# esp32-driver.net
KiCad netlist of a schematic drawn in EAGLE
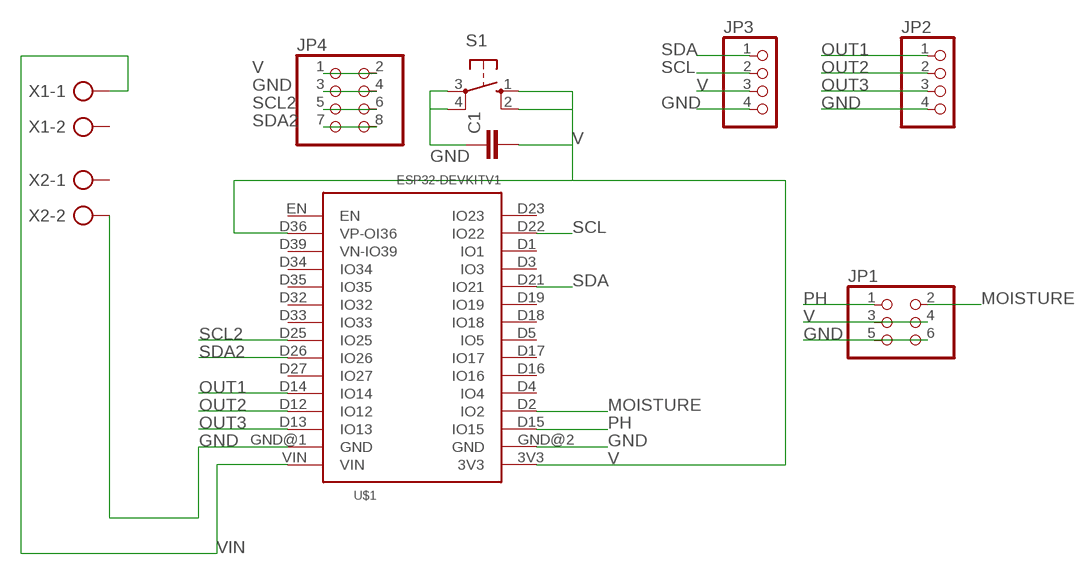
[diagram p0: schematic, sheet 1]

(export (version "E")
  (design (tool "Eeschema 10.0.6"))
  (components
    (comp (ref "C1")
      (value "C-EU050-030X075")
      (footprint "eagle-import:C050-030X075")
      (libsource (lib "eagle-import") (part "C-EU050-030X075"))
    )
    (comp (ref "JP1")
      (value "PINHD-2X3")
      (footprint "eagle-import:2X03")
      (libsource (lib "eagle-import") (part "PINHD-2X3"))
    )
    (comp (ref "JP2")
      (value "PINHD-1X4")
      (footprint "eagle-import:1X04")
      (libsource (lib "eagle-import") (part "PINHD-1X4"))
    )
    (comp (ref "JP3")
      (value "PINHD-1X4")
      (footprint "eagle-import:1X04")
      (libsource (lib "eagle-import") (part "PINHD-1X4"))
    )
    (comp (ref "JP4")
      (value "PINHD-2X4")
      (footprint "eagle-import:2X04")
      (libsource (lib "eagle-import") (part "PINHD-2X4"))
    )
    (comp (ref "S1")
      (value "10-XX")
      (footprint "eagle-import:B3F-10XX")
      (fields (field (name "MPN") "B3F-1000"))
      (libsource (lib "eagle-import") (part "10-XX"))
    )
    (comp (ref "U$1")
      (value "ESP32DEVKITV1")
      (footprint "eagle-import:ESP32-DEVKITV1")
      (libsource (lib "eagle-import") (part "ESP32DEVKITV1"))
    )
    (comp (ref "X1")
      (value "AK300/2")
      (footprint "eagle-import:AK300_2")
      (libsource (lib "eagle-import") (part "AK300/2"))
    )
    (comp (ref "X2")
      (value "AK300/2")
      (footprint "eagle-import:AK300_2")
      (libsource (lib "eagle-import") (part "AK300/2"))
    )
  )
  (nets
    (net (code "1") (name "/GND") (class "Default")
      (node (ref "C1") (pin "1") (pinfunction "1_1") (pintype "passive"))
      (node (ref "JP1") (pin "5") (pinfunction "5_5") (pintype "passive"))
      (node (ref "JP1") (pin "6") (pinfunction "6_6") (pintype "passive"))
      (node (ref "JP2") (pin "4") (pinfunction "4_4") (pintype "passive"))
      (node (ref "JP3") (pin "4") (pinfunction "4_4") (pintype "passive"))
      (node (ref "JP4") (pin "3") (pinfunction "3_3") (pintype "passive"))
      (node (ref "JP4") (pin "4") (pinfunction "4_4") (pintype "passive"))
      (node (ref "S1") (pin "3") (pinfunction "P_3") (pintype "passive"))
      (node (ref "S1") (pin "4") (pinfunction "P1_4") (pintype "passive"))
      (node (ref "U$1") (pin "GND@1") (pinfunction "GND_GND@1") (pintype "bidirectional"))
      (node (ref "U$1") (pin "GND@2") (pinfunction "GND_GND@2") (pintype "bidirectional"))
      (node (ref "X2") (pin "2") (pinfunction "KL_2") (pintype "passive"))
    )
    (net (code "2") (name "/MOISTURE") (class "Default")
      (node (ref "JP1") (pin "2") (pinfunction "2_2") (pintype "passive"))
      (node (ref "U$1") (pin "D2") (pinfunction "IO2_D2") (pintype "bidirectional"))
    )
    (net (code "3") (name "/OUT1") (class "Default")
      (node (ref "JP2") (pin "1") (pinfunction "1_1") (pintype "passive"))
      (node (ref "U$1") (pin "D14") (pinfunction "IO14_D14") (pintype "bidirectional"))
    )
    (net (code "4") (name "/OUT2") (class "Default")
      (node (ref "JP2") (pin "2") (pinfunction "2_2") (pintype "passive"))
      (node (ref "U$1") (pin "D12") (pinfunction "IO12_D12") (pintype "bidirectional"))
    )
    (net (code "5") (name "/OUT3") (class "Default")
      (node (ref "JP2") (pin "3") (pinfunction "3_3") (pintype "passive"))
      (node (ref "U$1") (pin "D13") (pinfunction "IO13_D13") (pintype "bidirectional"))
    )
    (net (code "6") (name "/PH") (class "Default")
      (node (ref "JP1") (pin "1") (pinfunction "1_1") (pintype "passive"))
      (node (ref "U$1") (pin "D15") (pinfunction "IO15_D15") (pintype "bidirectional"))
    )
    (net (code "7") (name "/SCL") (class "Default")
      (node (ref "JP3") (pin "2") (pinfunction "2_2") (pintype "passive"))
      (node (ref "U$1") (pin "D22") (pinfunction "IO22_D22") (pintype "bidirectional"))
    )
    (net (code "8") (name "/SCL2") (class "Default")
      (node (ref "JP4") (pin "5") (pinfunction "5_5") (pintype "passive"))
      (node (ref "JP4") (pin "6") (pinfunction "6_6") (pintype "passive"))
      (node (ref "U$1") (pin "D25") (pinfunction "IO25_D25") (pintype "bidirectional"))
    )
    (net (code "9") (name "/SDA") (class "Default")
      (node (ref "JP3") (pin "1") (pinfunction "1_1") (pintype "passive"))
      (node (ref "U$1") (pin "D21") (pinfunction "IO21_D21") (pintype "bidirectional"))
    )
    (net (code "10") (name "/SDA2") (class "Default")
      (node (ref "JP4") (pin "7") (pinfunction "7_7") (pintype "passive"))
      (node (ref "JP4") (pin "8") (pinfunction "8_8") (pintype "passive"))
      (node (ref "U$1") (pin "D26") (pinfunction "IO26_D26") (pintype "bidirectional"))
    )
    (net (code "11") (name "/V") (class "Default")
      (node (ref "C1") (pin "2") (pinfunction "2_2") (pintype "passive"))
      (node (ref "JP1") (pin "3") (pinfunction "3_3") (pintype "passive"))
      (node (ref "JP1") (pin "4") (pinfunction "4_4") (pintype "passive"))
      (node (ref "JP3") (pin "3") (pinfunction "3_3") (pintype "passive"))
      (node (ref "JP4") (pin "1") (pinfunction "1_1") (pintype "passive"))
      (node (ref "JP4") (pin "2") (pinfunction "2_2") (pintype "passive"))
      (node (ref "S1") (pin "1") (pinfunction "S_1") (pintype "passive"))
      (node (ref "S1") (pin "2") (pinfunction "S1_2") (pintype "passive"))
      (node (ref "U$1") (pin "3V3") (pinfunction "3V3_3V3") (pintype "bidirectional"))
      (node (ref "U$1") (pin "D36") (pinfunction "VP-OI36_D36") (pintype "bidirectional"))
    )
    (net (code "12") (name "/VIN") (class "Default")
      (node (ref "U$1") (pin "VIN") (pinfunction "VIN_VIN") (pintype "bidirectional"))
      (node (ref "X1") (pin "1") (pinfunction "KL_1") (pintype "passive"))
    )
    (net (code "13") (name "unconnected-(U$1-IO1-PadD1)") (class "Default")
      (node (ref "U$1") (pin "D1") (pinfunction "IO1_D1") (pintype "bidirectional"))
    )
    (net (code "14") (name "unconnected-(U$1-IO3-PadD3)") (class "Default")
      (node (ref "U$1") (pin "D3") (pinfunction "IO3_D3") (pintype "bidirectional"))
    )
    (net (code "15") (name "unconnected-(U$1-IO4-PadD4)") (class "Default")
      (node (ref "U$1") (pin "D4") (pinfunction "IO4_D4") (pintype "bidirectional"))
    )
    (net (code "16") (name "unconnected-(U$1-IO5-PadD5)") (class "Default")
      (node (ref "U$1") (pin "D5") (pinfunction "IO5_D5") (pintype "bidirectional"))
    )
    (net (code "17") (name "unconnected-(U$1-IO16-PadD16)") (class "Default")
      (node (ref "U$1") (pin "D16") (pinfunction "IO16_D16") (pintype "bidirectional"))
    )
    (net (code "18") (name "unconnected-(U$1-IO17-PadD17)") (class "Default")
      (node (ref "U$1") (pin "D17") (pinfunction "IO17_D17") (pintype "bidirectional"))
    )
    (net (code "19") (name "unconnected-(U$1-IO18-PadD18)") (class "Default")
      (node (ref "U$1") (pin "D18") (pinfunction "IO18_D18") (pintype "bidirectional"))
    )
    (net (code "20") (name "unconnected-(U$1-IO19-PadD19)") (class "Default")
      (node (ref "U$1") (pin "D19") (pinfunction "IO19_D19") (pintype "bidirectional"))
    )
    (net (code "21") (name "unconnected-(U$1-IO23-PadD23)") (class "Default")
      (node (ref "U$1") (pin "D23") (pinfunction "IO23_D23") (pintype "bidirectional"))
    )
    (net (code "22") (name "unconnected-(U$1-IO27-PadD27)") (class "Default")
      (node (ref "U$1") (pin "D27") (pinfunction "IO27_D27") (pintype "bidirectional"))
    )
    (net (code "23") (name "unconnected-(U$1-IO32-PadD32)") (class "Default")
      (node (ref "U$1") (pin "D32") (pinfunction "IO32_D32") (pintype "bidirectional"))
    )
    (net (code "24") (name "unconnected-(U$1-IO33-PadD33)") (class "Default")
      (node (ref "U$1") (pin "D33") (pinfunction "IO33_D33") (pintype "bidirectional"))
    )
    (net (code "25") (name "unconnected-(U$1-IO34-PadD34)") (class "Default")
      (node (ref "U$1") (pin "D34") (pinfunction "IO34_D34") (pintype "bidirectional"))
    )
    (net (code "26") (name "unconnected-(U$1-IO35-PadD35)") (class "Default")
      (node (ref "U$1") (pin "D35") (pinfunction "IO35_D35") (pintype "bidirectional"))
    )
    (net (code "27") (name "unconnected-(U$1-PadEN)") (class "Default")
      (node (ref "U$1") (pin "EN") (pinfunction "EN_EN") (pintype "bidirectional"))
    )
    (net (code "28") (name "unconnected-(U$1-VN-IO39-PadD39)") (class "Default")
      (node (ref "U$1") (pin "D39") (pinfunction "VN-IO39_D39") (pintype "bidirectional"))
    )
    (net (code "29") (name "unconnected-(X1B-KL-Pad2)") (class "Default")
      (node (ref "X1") (pin "2") (pinfunction "KL_2") (pintype "passive"))
    )
    (net (code "30") (name "unconnected-(X2A-KL-Pad1)") (class "Default")
      (node (ref "X2") (pin "1") (pinfunction "KL_1") (pintype "passive"))
    )
  )
)
